# EASYEDA_JSON.net
KiCad netlist of a schematic drawn in EasyEDA
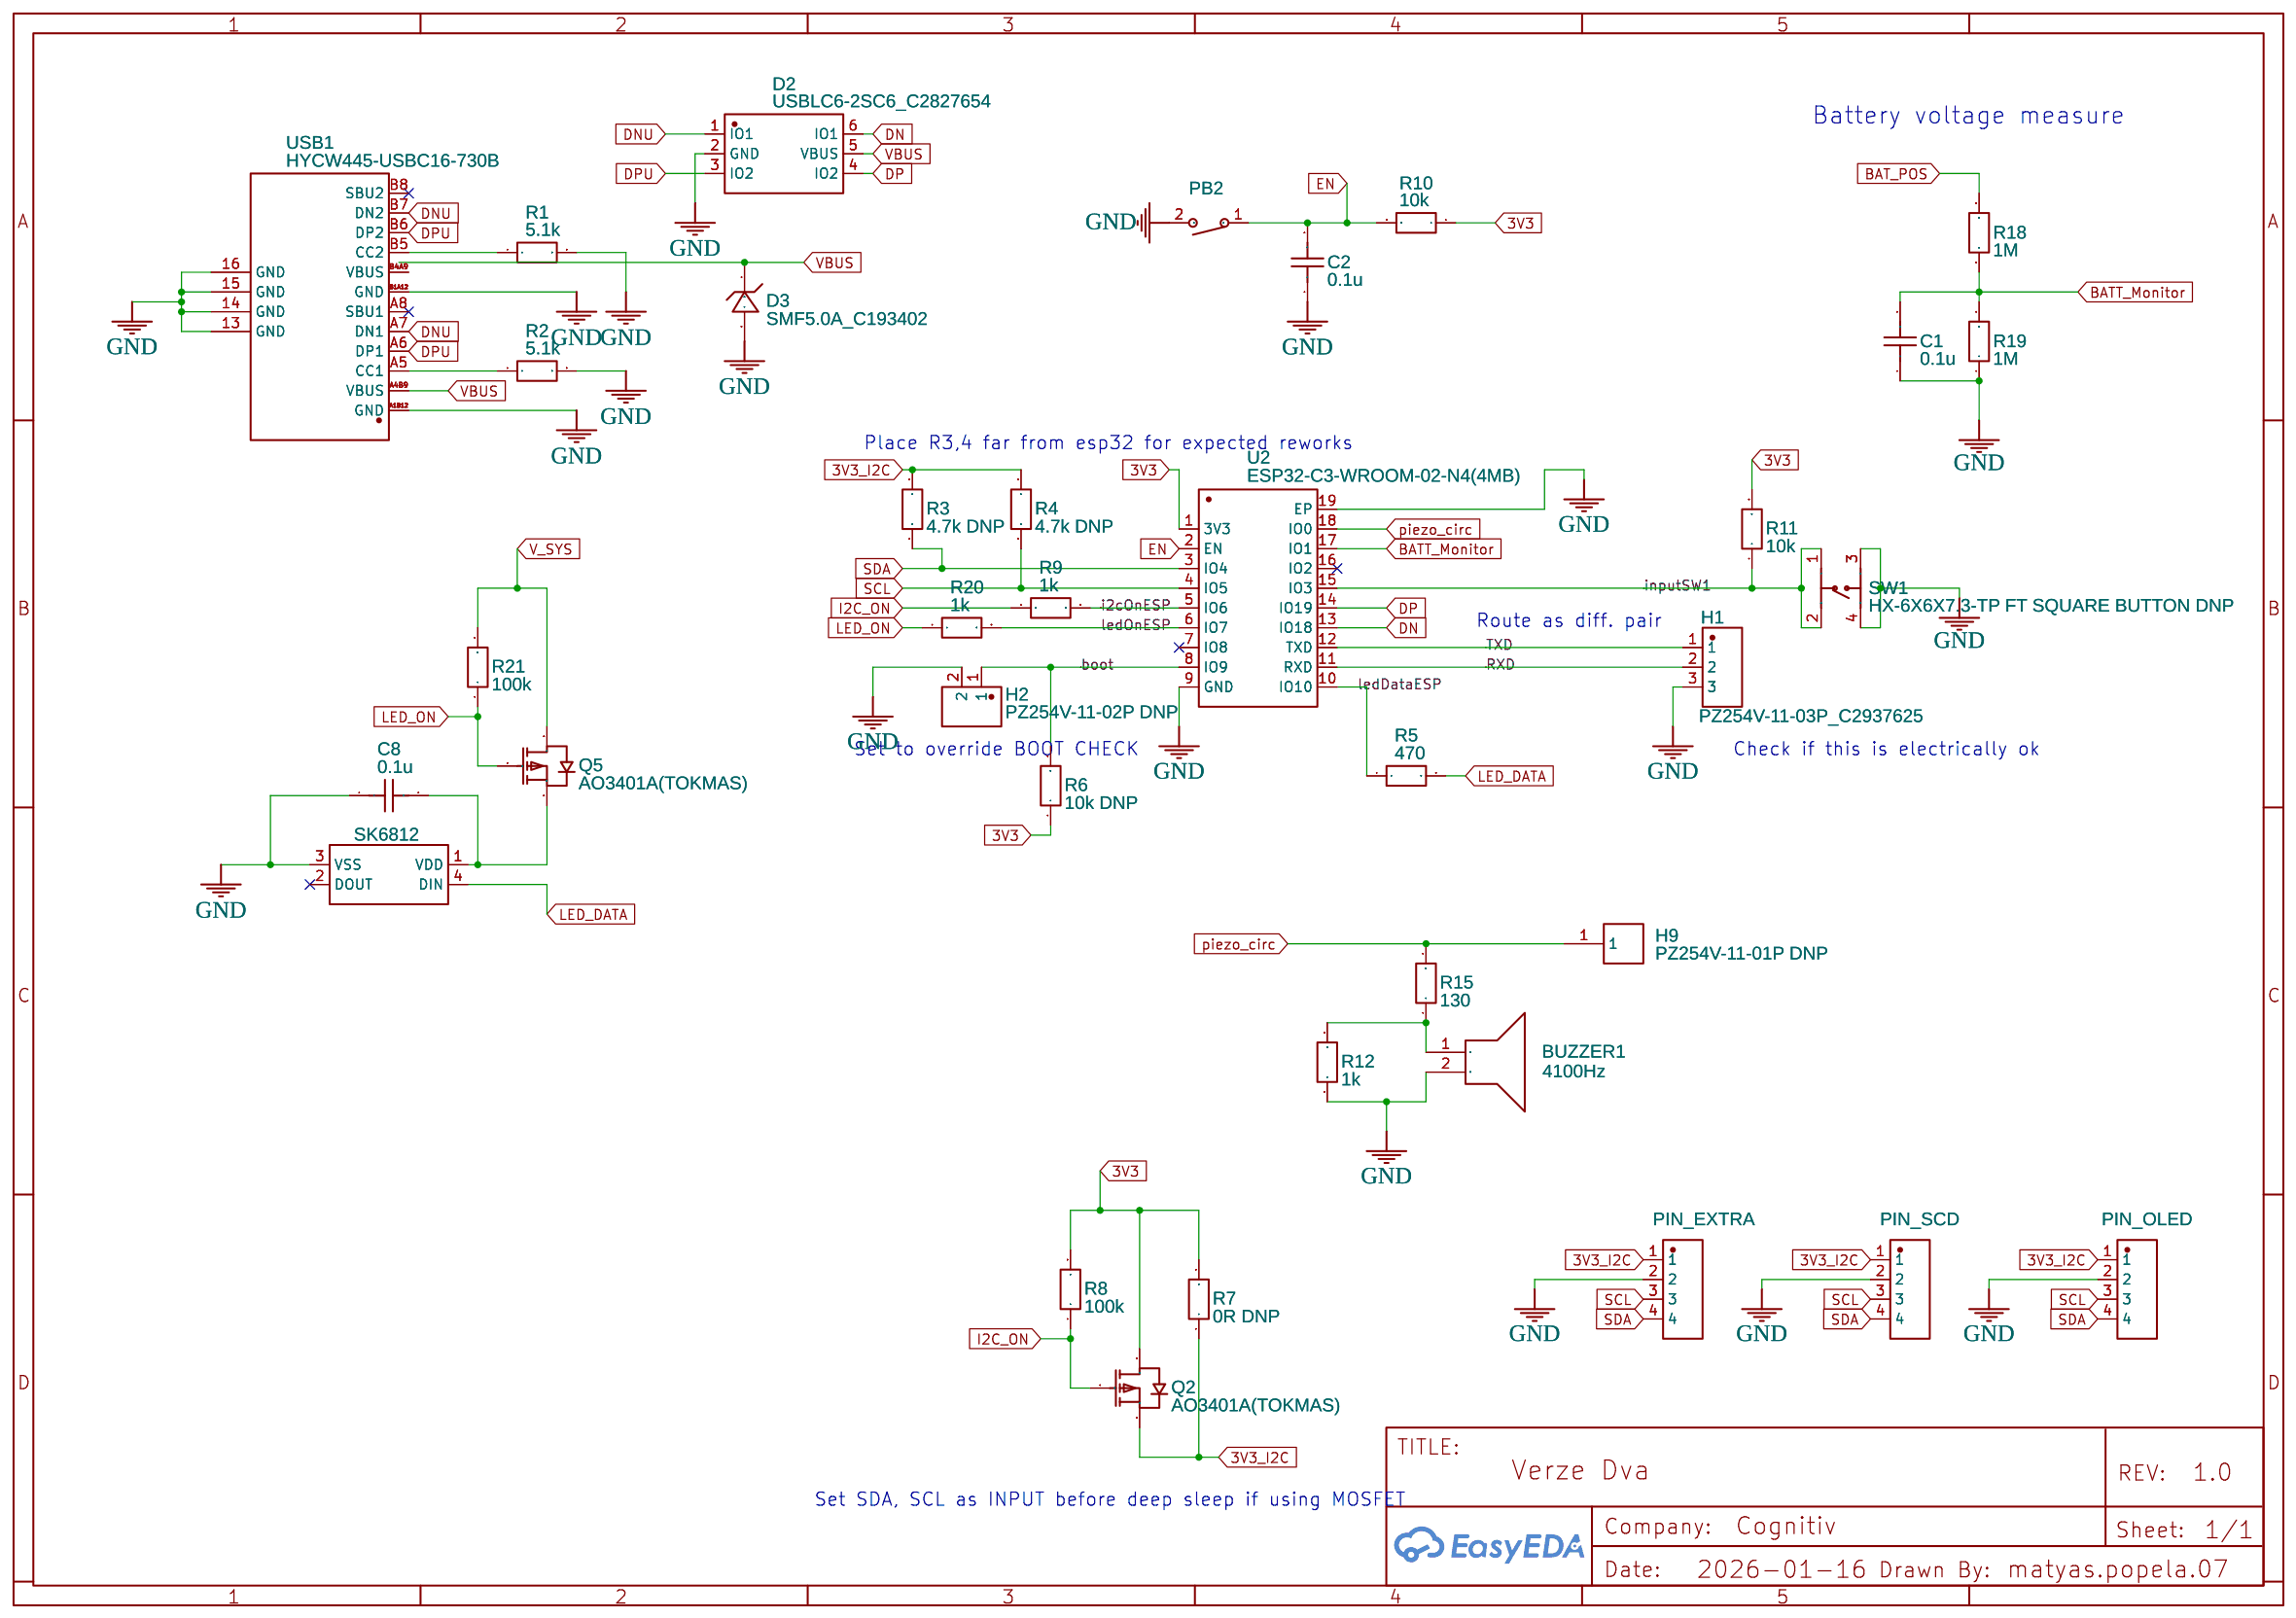
[diagram p0: Mainboard_C3]
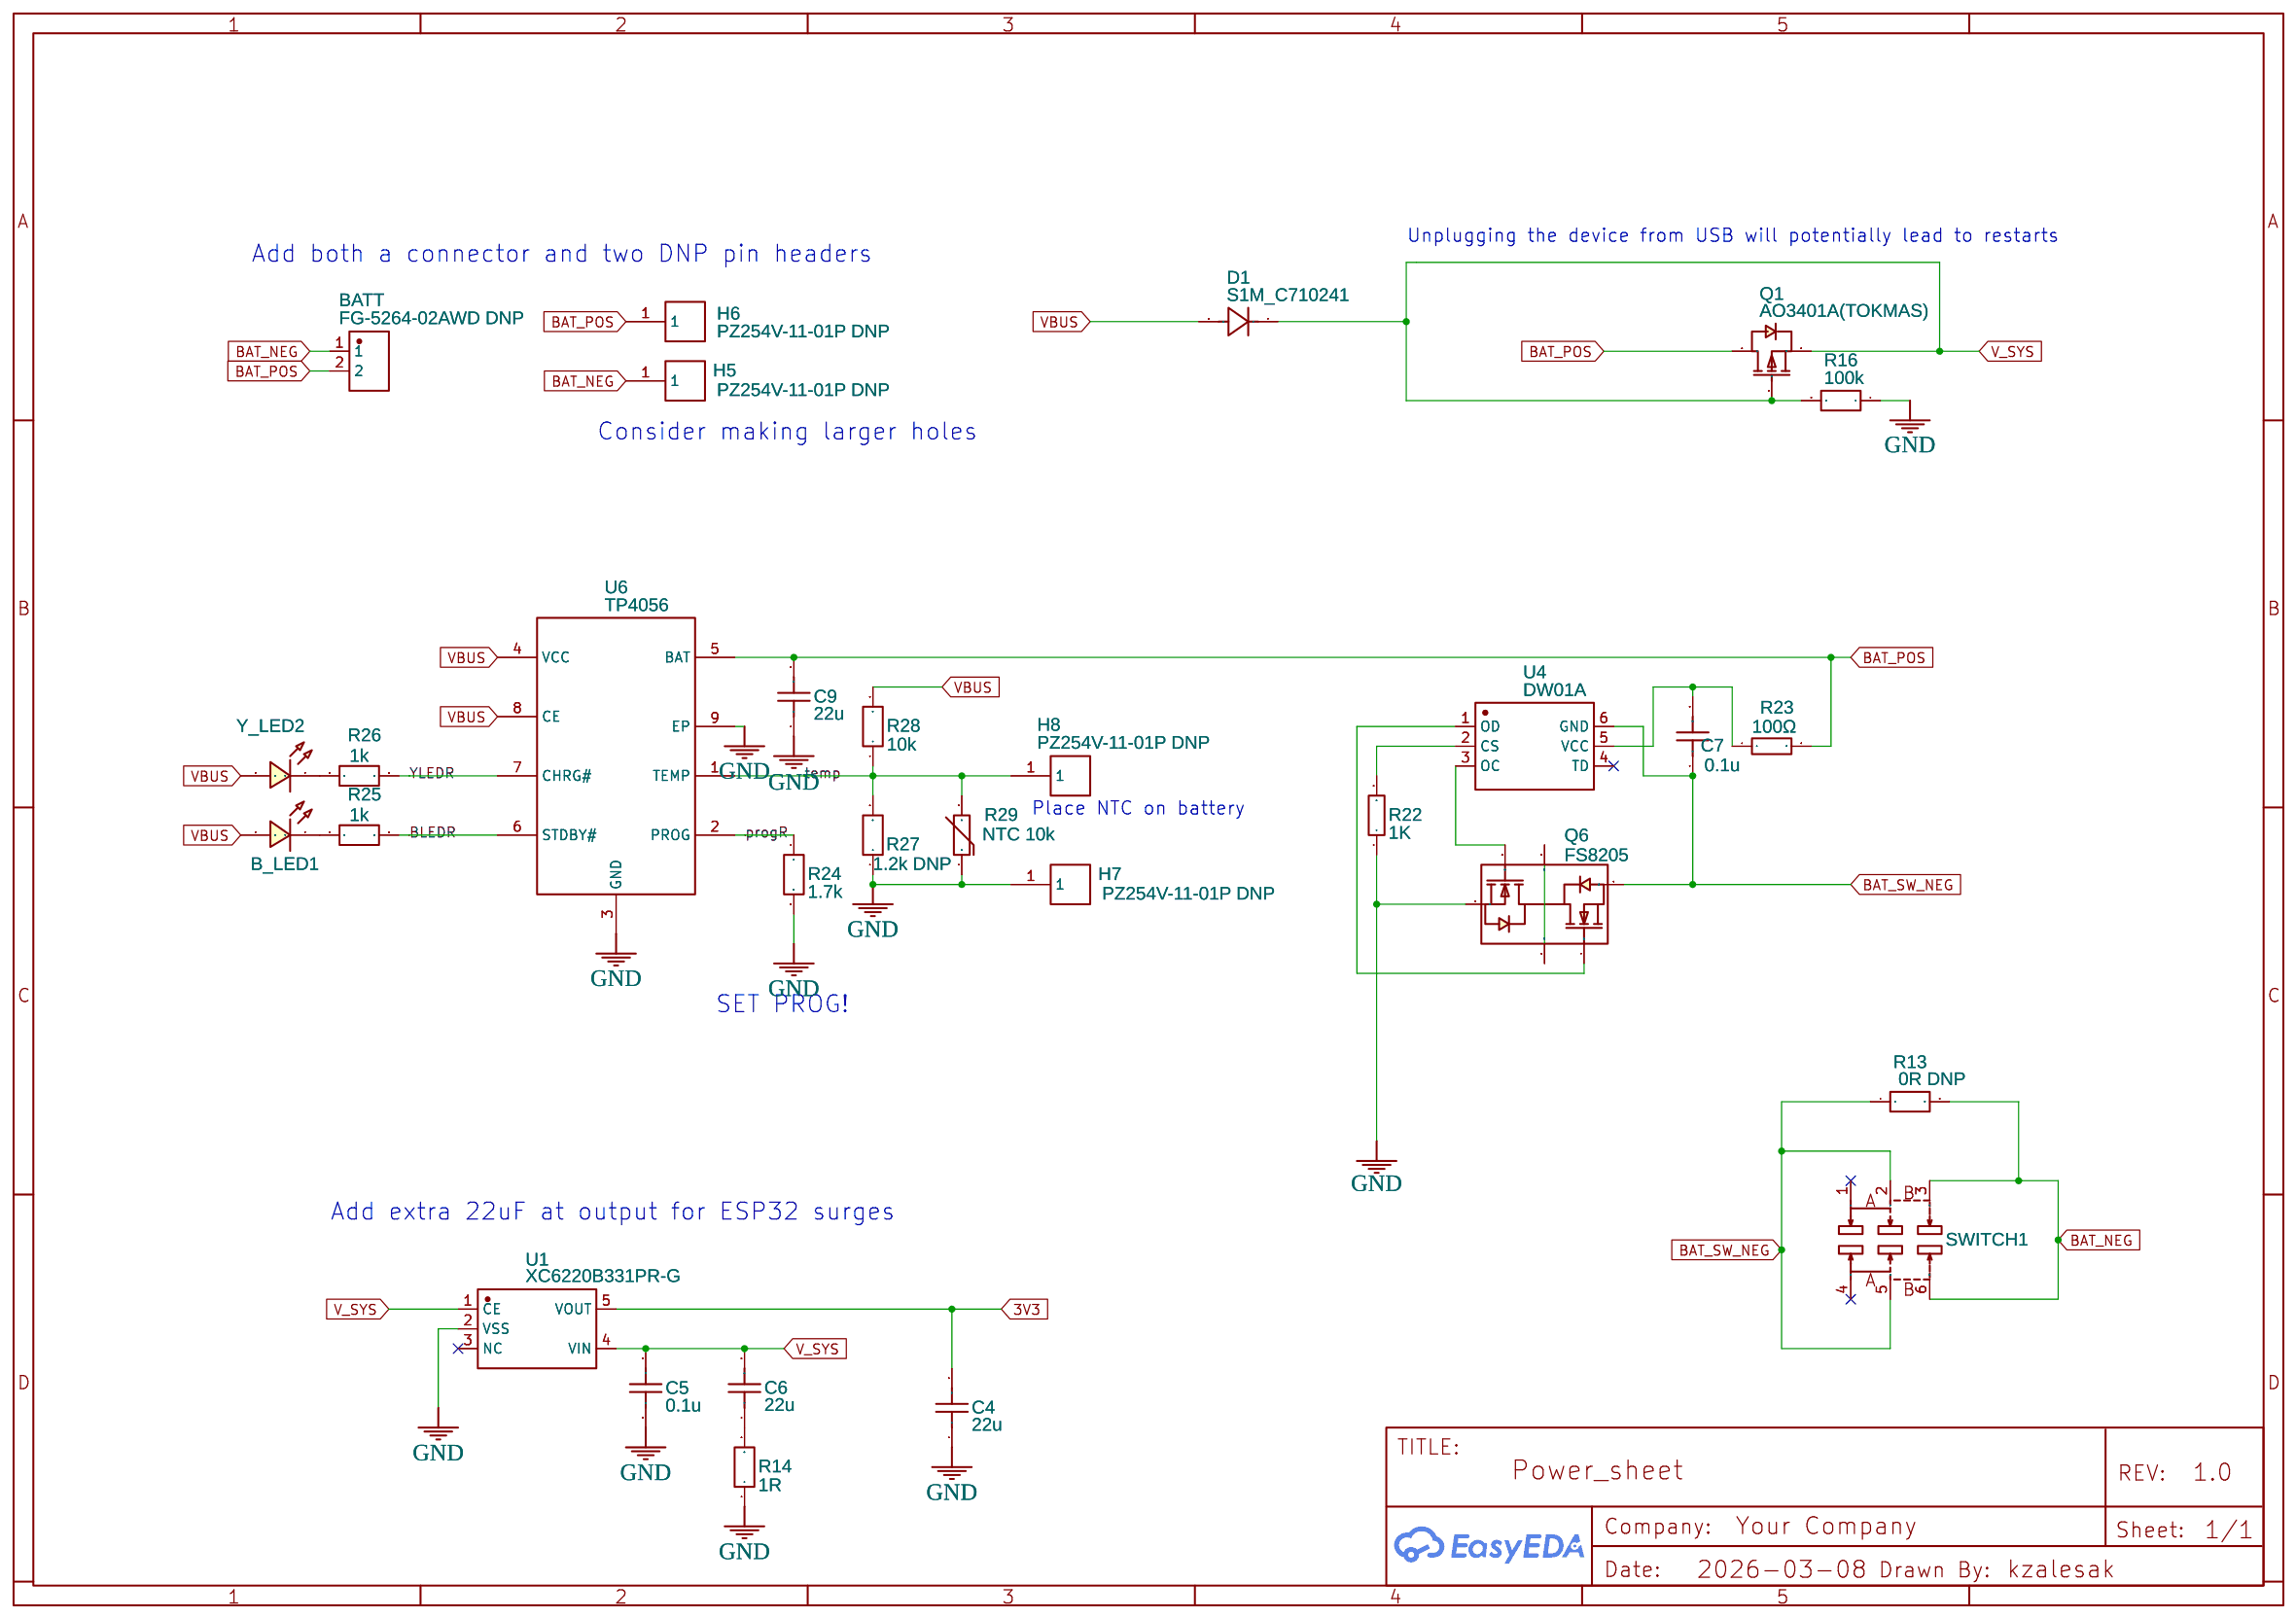
[diagram p1: Power_Management]

(export (version "E")
  (design (tool "Eeschema 10.0.6"))
  (components
    (comp (ref "BUZZER1")
      (value "4100Hz")
      (fields (field (name "Manufacturer Part") "FUET-1109") (field (name "Manufacturer") "FUET(福声科技)"))
      (libsource (lib "") (part "FST-1109"))
    )
    (comp (ref "C1")
      (value "0.1u")
      (fields
        (field (name "Manufacturer Part") "CC0603KRX7R9BB104")
        (field (name "Manufacturer") "YAGEO(国巨)")
      )
      (libsource (lib "") (part "C_0603_US"))
    )
    (comp (ref "C2")
      (value "0.1u")
      (fields
        (field (name "Manufacturer Part") "CC0603KRX7R9BB104")
        (field (name "Manufacturer") "YAGEO(国巨)")
      )
      (libsource (lib "") (part "C_0603_US"))
    )
    (comp (ref "C8")
      (value "0.1u")
      (fields
        (field (name "Manufacturer Part") "CC0603KRX7R9BB104")
        (field (name "Manufacturer") "YAGEO(国巨)")
      )
      (libsource (lib "") (part "C_0603_US_1"))
    )
    (comp (ref "D2")
      (value "USBLC6-2SC6_C2827654")
      (fields
        (field (name "Manufacturer Part") "USBLC6-2SC6")
        (field (name "Manufacturer") "TECH PUBLIC(台舟)")
      )
      (libsource (lib "") (part "USBLC6-2SC6_C2827654"))
    )
    (comp (ref "D3")
      (value "SMF5.0A_C193402")
      (fields (field (name "Manufacturer Part") "SMF5.0A") (field (name "Manufacturer") "MDD(辰达半导体)"))
      (libsource (lib "") (part "SMF5.0A_C193402"))
    )
    (comp (ref "H1")
      (value "PZ254V-11-03P_C2937625")
      (fields (field (name "Manufacturer Part") "PZ254V-11-03P") (field (name "Manufacturer") "XFCN(兴飞)"))
      (libsource (lib "") (part "PZ254V-11-03P_C2937625"))
    )
    (comp (ref "H2")
      (value "PZ254V-11-02P DNP")
      (fields (field (name "Manufacturer Part") "PZ254V-11-02P") (field (name "Manufacturer") "XFCN(兴飞)"))
      (libsource (lib "") (part "PZ254V-11-02P"))
    )
    (comp (ref "H9")
      (value "PZ254V-11-01P DNP")
      (fields (field (name "Manufacturer Part") "PZ254V-11-01P") (field (name "Manufacturer") "XFCN(兴飞)"))
      (libsource (lib "") (part "PZ254V-11-01P"))
    )
    (comp (ref "PB2")
      (value "HX 3X4X2-2P-1.6N TACTILE SWITCH DNP")
      (fields
        (field (name "Manufacturer Part") "HX 3x4x2-2P-1.6N TACTILE SWITCH")
        (field (name "Manufacturer") "hanxia(韩下)")
      )
      (libsource (lib "") (part "HX 3X4X2-2P-1.6N TACTILE SWITCH"))
    )
    (comp (ref "PIN_EXTRA")
      (value "2.54-1*4")
      (fields (field (name "Manufacturer") "ZHOURI(洲日)"))
      (libsource (lib "") (part "2.54-1*4_1"))
    )
    (comp (ref "PIN_OLED")
      (value "2.54-1*4")
      (fields (field (name "Manufacturer") "ZHOURI(洲日)"))
      (libsource (lib "") (part "2.54-1*4_2"))
    )
    (comp (ref "PIN_SCD")
      (value "2.54-1*4")
      (fields (field (name "Manufacturer") "ZHOURI(洲日)"))
      (libsource (lib "") (part "2.54-1*4"))
    )
    (comp (ref "Q2")
      (value "AO3401A(TOKMAS)")
      (fields (field (name "Manufacturer") "Tokmas(托克马斯)"))
      (libsource (lib "") (part "AO3401A(TOKMAS)"))
    )
    (comp (ref "Q5")
      (value "AO3401A(TOKMAS)")
      (fields (field (name "Manufacturer") "Tokmas(托克马斯)"))
      (libsource (lib "") (part "AO3401A(TOKMAS)"))
    )
    (comp (ref "R1") (value "5.1k") (libsource (lib "") (part "R_0603_EU_1")))
    (comp (ref "R2") (value "5.1k") (libsource (lib "") (part "R_0603_EU_1")))
    (comp (ref "R3") (value "4.7k DNP") (libsource (lib "") (part "R_0603_EU")))
    (comp (ref "R4") (value "4.7k DNP") (libsource (lib "") (part "R_0603_EU")))
    (comp (ref "R5") (value "470") (libsource (lib "") (part "R_0603_EU_1")))
    (comp (ref "R6") (value "10k DNP") (libsource (lib "") (part "R_0603_EU")))
    (comp (ref "R7") (value "0R DNP") (libsource (lib "") (part "R_0603_EU")))
    (comp (ref "R8") (value "100k") (libsource (lib "") (part "R_0603_EU")))
    (comp (ref "R9") (value "1k") (libsource (lib "") (part "R_0603_EU_1")))
    (comp (ref "R10") (value "10k") (libsource (lib "") (part "R_0603_EU_2")))
    (comp (ref "R11") (value "10k") (libsource (lib "") (part "R_0603_EU")))
    (comp (ref "R12") (value "1k") (libsource (lib "") (part "R_0603_EU")))
    (comp (ref "R15") (value "130") (libsource (lib "") (part "R_0603_EU")))
    (comp (ref "R18") (value "1M") (libsource (lib "") (part "R_0603_EU")))
    (comp (ref "R19") (value "1M") (libsource (lib "") (part "R_0603_EU")))
    (comp (ref "R20") (value "1k") (libsource (lib "") (part "R_0603_EU_1")))
    (comp (ref "R21") (value "100k") (libsource (lib "") (part "R_0603_EU")))
    (comp (ref "SK6812")
      (value "SK6812_C5378720")
      (fields (field (name "Manufacturer Part") "SK6812") (field (name "Manufacturer") "欧思科光电"))
      (libsource (lib "") (part "SK6812_C5378720"))
    )
    (comp (ref "SW1")
      (value "HX-6X6X7.3-TP FT SQUARE BUTTON DNP")
      (fields
        (field (name "Manufacturer Part") "HX-6x6x7.3-TP FT square button")
        (field (name "Manufacturer") "hanxia(韩下)")
      )
      (libsource (lib "") (part "HX-6X6X7.3-TP FT SQUARE BUTTON"))
    )
    (comp (ref "U2")
      (value "ESP32-C3-WROOM-02-N4(4MB)")
      (fields
        (field (name "Manufacturer Part") "ESP32-C3-WROOM-02-N4")
        (field (name "Manufacturer") "ESPRESSIF(乐鑫)")
      )
      (libsource (lib "") (part "ESP32-C3-WROOM-02-N4(4MB)"))
    )
    (comp (ref "USB1")
      (value "HYCW445-USBC16-730B")
      (fields (field (name "Manufacturer") "华宇创"))
      (libsource (lib "") (part "HYCW445-USBC16-730B"))
    )
    (comp (ref "BATT")
      (value "FG-5264-02AWD DNP")
      (fields (field (name "Manufacturer Part") "FG-5264-02AWD") (field (name "Manufacturer") "FG(富港)"))
      (libsource (lib "") (part "FG-5264-02AWD"))
    )
    (comp (ref "B_LED1")
      (value "LED-0603_R")
      (fields
        (field (name "Manufacturer Part") "19-217/R6C-AL1M2VY/3T")
        (field (name "Manufacturer") "EVERLIGHT(台湾亿光)")
      )
      (libsource (lib "") (part "LED-0603_R_1"))
    )
    (comp (ref "C4")
      (value "22u")
      (fields
        (field (name "Manufacturer Part") "CL21A226MAQNNNE")
        (field (name "Manufacturer") "SAMSUNG(三星)")
      )
      (libsource (lib "") (part "CL21A226MAQNNNE"))
    )
    (comp (ref "C5")
      (value "0.1u")
      (fields
        (field (name "Manufacturer Part") "CC0603KRX7R9BB104")
        (field (name "Manufacturer") "YAGEO(国巨)")
      )
      (libsource (lib "") (part "C_0603_US"))
    )
    (comp (ref "C6")
      (value "22u")
      (fields
        (field (name "Manufacturer Part") "CL21A226MAQNNNE")
        (field (name "Manufacturer") "SAMSUNG(三星)")
      )
      (libsource (lib "") (part "CL21A226MAQNNNE"))
    )
    (comp (ref "C7")
      (value "0.1u")
      (fields
        (field (name "Manufacturer Part") "CC0603KRX7R9BB104")
        (field (name "Manufacturer") "YAGEO(国巨)")
      )
      (libsource (lib "") (part "C_0603_US"))
    )
    (comp (ref "C9")
      (value "22u")
      (fields
        (field (name "Manufacturer Part") "CL21A226MAQNNNE")
        (field (name "Manufacturer") "SAMSUNG(三星)")
      )
      (libsource (lib "") (part "CL21A226MAQNNNE"))
    )
    (comp (ref "D1")
      (value "S1M_C710241")
      (fields (field (name "Manufacturer Part") "S1M") (field (name "Manufacturer") "DIODES(美台)"))
      (libsource (lib "") (part "S1M_C710241"))
    )
    (comp (ref "H5")
      (value "PZ254V-11-01P DNP")
      (fields (field (name "Manufacturer Part") "PZ254V-11-01P") (field (name "Manufacturer") "XFCN(兴飞)"))
      (libsource (lib "") (part "PZ254V-11-01P"))
    )
    (comp (ref "H6")
      (value "PZ254V-11-01P DNP")
      (fields (field (name "Manufacturer Part") "PZ254V-11-01P") (field (name "Manufacturer") "XFCN(兴飞)"))
      (libsource (lib "") (part "PZ254V-11-01P"))
    )
    (comp (ref "H7")
      (value "PZ254V-11-01P DNP")
      (fields (field (name "Manufacturer Part") "PZ254V-11-01P") (field (name "Manufacturer") "XFCN(兴飞)"))
      (libsource (lib "") (part "PZ254V-11-01P"))
    )
    (comp (ref "H8")
      (value "PZ254V-11-01P DNP")
      (fields (field (name "Manufacturer Part") "PZ254V-11-01P") (field (name "Manufacturer") "XFCN(兴飞)"))
      (libsource (lib "") (part "PZ254V-11-01P"))
    )
    (comp (ref "Q1")
      (value "AO3401A(TOKMAS)")
      (fields (field (name "Manufacturer") "Tokmas(托克马斯)"))
      (libsource (lib "") (part "AO3401A(TOKMAS)"))
    )
    (comp (ref "Q6")
      (value "FS8205")
      (fields (field (name "Manufacturer") "FORTUNE"))
      (libsource (lib "") (part "Unknown_775_-355"))
    )
    (comp (ref "R13") (value "0R DNP") (libsource (lib "") (part "R_0603_EU_1")))
    (comp (ref "R14") (value "1R") (libsource (lib "") (part "R_0603_EU_2")))
    (comp (ref "R16") (value "100k") (libsource (lib "") (part "R_0603_EU")))
    (comp (ref "R22")
      (value "1K")
      (fields (field (name "Manufacturer Part") "ERJ3GEYJ102V") (field (name "Manufacturer") "PANASONIC"))
      (libsource (lib "") (part "ERJ3GEYJ102V"))
    )
    (comp (ref "R23")
      (value "100Ω")
      (fields (field (name "Manufacturer Part") "0603WAJ0101T5E") (field (name "Manufacturer") "UniOhm"))
      (libsource (lib "") (part "0603WAJ0101T5E"))
    )
    (comp (ref "R24") (value "1.7k") (libsource (lib "") (part "R_0603_EU_3")))
    (comp (ref "R25") (value "1k") (libsource (lib "") (part "R_0603_EU_1")))
    (comp (ref "R26") (value "1k") (libsource (lib "") (part "R_0603_EU_1")))
    (comp (ref "R27") (value "1.2k DNP") (libsource (lib "") (part "R_0603_EU_2")))
    (comp (ref "R28") (value "10k") (libsource (lib "") (part "R_0603_EU_2")))
    (comp (ref "R29")
      (value "NTC 10k")
      (fields (field (name "Manufacturer Part") "CMFB103F3950FANT") (field (name "Manufacturer") "FH(风华)"))
      (libsource (lib "") (part "CMFB103F3950FANT"))
    )
    (comp (ref "SWITCH1")
      (value "MST22D18G2 125 DNP")
      (fields
        (field (name "Manufacturer Part") "MST22D18G2 125")
        (field (name "Manufacturer") "SHOU HAN(首韩)")
      )
      (libsource (lib "") (part "MST22D18G2 125"))
    )
    (comp (ref "U1")
      (value "XC6220B331PR-G")
      (fields (field (name "Manufacturer") "TOREX(特瑞仕)"))
      (libsource (lib "") (part "XC6220B331PR-G"))
    )
    (comp (ref "U4")
      (value "DW01A")
      (fields (field (name "Manufacturer") "PUOLOP"))
      (libsource (lib "") (part "Unknown_770_-435"))
    )
    (comp (ref "U6")
      (value "TP4056")
      (fields
        (field (name "Manufacturer Part") "TP4056-42-ESOP8")
        (field (name "Manufacturer") "TOPPOWER(南京拓微)")
      )
      (libsource (lib "") (part "TP4056"))
    )
    (comp (ref "Y_LED2")
      (value "LED-0603_R")
      (fields
        (field (name "Manufacturer Part") "19-217/R6C-AL1M2VY/3T")
        (field (name "Manufacturer") "EVERLIGHT(台湾亿光)")
      )
      (libsource (lib "") (part "LED-0603_R"))
    )
  )
  (nets
    (net (code "1") (name "3V3") (class "Default")
      (node (ref "C4") (pin "2") (pinfunction "2_2") (pintype "unspecified"))
      (node (ref "Q2") (pin "3") (pinfunction "D_3") (pintype "unspecified"))
      (node (ref "R10") (pin "1") (pinfunction "1_1") (pintype "unspecified"))
      (node (ref "R11") (pin "2") (pinfunction "2_2") (pintype "unspecified"))
      (node (ref "R6") (pin "1") (pinfunction "1_1") (pintype "unspecified"))
      (node (ref "R7") (pin "2") (pinfunction "2_2") (pintype "unspecified"))
      (node (ref "R8") (pin "2") (pinfunction "2_2") (pintype "unspecified"))
      (node (ref "U1") (pin "5") (pinfunction "VOUT_5") (pintype "unspecified"))
      (node (ref "U2") (pin "1") (pinfunction "3V3_1") (pintype "unspecified"))
    )
    (net (code "2") (name "3V3_I2C") (class "Default")
      (node (ref "PIN_EXTRA") (pin "1") (pinfunction "1_1") (pintype "unspecified"))
      (node (ref "PIN_OLED") (pin "1") (pinfunction "1_1") (pintype "unspecified"))
      (node (ref "PIN_SCD") (pin "1") (pinfunction "1_1") (pintype "unspecified"))
      (node (ref "Q2") (pin "2") (pinfunction "S_2") (pintype "unspecified"))
      (node (ref "R3") (pin "2") (pinfunction "2_2") (pintype "unspecified"))
      (node (ref "R4") (pin "2") (pinfunction "2_2") (pintype "unspecified"))
      (node (ref "R7") (pin "1") (pinfunction "1_1") (pintype "unspecified"))
    )
    (net (code "3") (name "BATT_Monitor") (class "Default")
      (node (ref "C1") (pin "2") (pinfunction "2_2") (pintype "unspecified"))
      (node (ref "R18") (pin "1") (pinfunction "1_1") (pintype "unspecified"))
      (node (ref "R19") (pin "2") (pinfunction "2_2") (pintype "unspecified"))
      (node (ref "U2") (pin "17") (pinfunction "IO1_17") (pintype "unspecified"))
    )
    (net (code "4") (name "BAT_NEG") (class "Default")
      (node (ref "BATT") (pin "1") (pinfunction "1_1") (pintype "unspecified"))
      (node (ref "H5") (pin "1") (pinfunction "1_1") (pintype "unspecified"))
      (node (ref "R13") (pin "2") (pinfunction "2_2") (pintype "unspecified"))
      (node (ref "SWITCH1") (pin "3") (pinfunction "3_3") (pintype "unspecified"))
      (node (ref "SWITCH1") (pin "6") (pinfunction "6_6") (pintype "unspecified"))
    )
    (net (code "5") (name "BAT_POS") (class "Default")
      (node (ref "BATT") (pin "2") (pinfunction "2_2") (pintype "unspecified"))
      (node (ref "C9") (pin "2") (pinfunction "2_2") (pintype "unspecified"))
      (node (ref "H6") (pin "1") (pinfunction "1_1") (pintype "unspecified"))
      (node (ref "Q1") (pin "3") (pinfunction "D_3") (pintype "unspecified"))
      (node (ref "R18") (pin "2") (pinfunction "2_2") (pintype "unspecified"))
      (node (ref "R23") (pin "2") (pinfunction "2_2") (pintype "input"))
      (node (ref "U6") (pin "5") (pinfunction "BAT_5") (pintype "unspecified"))
    )
    (net (code "6") (name "BAT_SW_NEG") (class "Default")
      (node (ref "C7") (pin "1") (pinfunction "1_1") (pintype "unspecified"))
      (node (ref "Q6") (pin "3") (pinfunction "S2_3") (pintype "unspecified"))
      (node (ref "R13") (pin "1") (pinfunction "1_1") (pintype "unspecified"))
      (node (ref "SWITCH1") (pin "2") (pinfunction "2_2") (pintype "unspecified"))
      (node (ref "SWITCH1") (pin "5") (pinfunction "5_5") (pintype "unspecified"))
      (node (ref "U4") (pin "6") (pinfunction "GND_6") (pintype "unspecified"))
    )
    (net (code "7") (name "BLEDR") (class "Default")
      (node (ref "R25") (pin "2") (pinfunction "2_2") (pintype "unspecified"))
      (node (ref "U6") (pin "6") (pinfunction "STDBY#_6") (pintype "unspecified"))
    )
    (net (code "8") (name "DN") (class "Default")
      (node (ref "D2") (pin "6") (pinfunction "IO1_6") (pintype "unspecified"))
      (node (ref "U2") (pin "13") (pinfunction "IO18_13") (pintype "unspecified"))
    )
    (net (code "9") (name "DNU") (class "Default")
      (node (ref "D2") (pin "1") (pinfunction "IO1_1") (pintype "unspecified"))
      (node (ref "USB1") (pin "A7") (pinfunction "DN1_A7") (pintype "unspecified"))
      (node (ref "USB1") (pin "B7") (pinfunction "DN2_B7") (pintype "unspecified"))
    )
    (net (code "10") (name "DP") (class "Default")
      (node (ref "D2") (pin "4") (pinfunction "IO2_4") (pintype "unspecified"))
      (node (ref "U2") (pin "14") (pinfunction "IO19_14") (pintype "unspecified"))
    )
    (net (code "11") (name "DPU") (class "Default")
      (node (ref "D2") (pin "3") (pinfunction "IO2_3") (pintype "unspecified"))
      (node (ref "USB1") (pin "A6") (pinfunction "DP1_A6") (pintype "unspecified"))
      (node (ref "USB1") (pin "B6") (pinfunction "DP2_B6") (pintype "unspecified"))
    )
    (net (code "12") (name "EN") (class "Default")
      (node (ref "C2") (pin "2") (pinfunction "2_2") (pintype "unspecified"))
      (node (ref "PB2") (pin "1") (pinfunction "1_1") (pintype "unspecified"))
      (node (ref "R10") (pin "2") (pinfunction "2_2") (pintype "unspecified"))
      (node (ref "U2") (pin "2") (pinfunction "EN_2") (pintype "unspecified"))
    )
    (net (code "13") (name "GND") (class "Default")
      (node (ref "BUZZER1") (pin "2") (pinfunction "2_2") (pintype "unspecified"))
      (node (ref "C1") (pin "1") (pinfunction "1_1") (pintype "unspecified"))
      (node (ref "C2") (pin "1") (pinfunction "1_1") (pintype "unspecified"))
      (node (ref "C4") (pin "1") (pinfunction "1_1") (pintype "unspecified"))
      (node (ref "C5") (pin "1") (pinfunction "1_1") (pintype "unspecified"))
      (node (ref "C8") (pin "1") (pinfunction "1_1") (pintype "unspecified"))
      (node (ref "C9") (pin "1") (pinfunction "1_1") (pintype "unspecified"))
      (node (ref "D2") (pin "2") (pinfunction "GND_2") (pintype "unspecified"))
      (node (ref "D3") (pin "2") (pinfunction "A_2") (pintype "unspecified"))
      (node (ref "H1") (pin "3") (pinfunction "3_3") (pintype "unspecified"))
      (node (ref "H2") (pin "2") (pinfunction "2_2") (pintype "unspecified"))
      (node (ref "H7") (pin "1") (pinfunction "1_1") (pintype "unspecified"))
      (node (ref "PB2") (pin "2") (pinfunction "2_2") (pintype "unspecified"))
      (node (ref "PIN_EXTRA") (pin "2") (pinfunction "2_2") (pintype "unspecified"))
      (node (ref "PIN_OLED") (pin "2") (pinfunction "2_2") (pintype "unspecified"))
      (node (ref "PIN_SCD") (pin "2") (pinfunction "2_2") (pintype "unspecified"))
      (node (ref "Q6") (pin "1") (pinfunction "S1_1") (pintype "unspecified"))
      (node (ref "R1") (pin "2") (pinfunction "2_2") (pintype "unspecified"))
      (node (ref "R12") (pin "1") (pinfunction "1_1") (pintype "unspecified"))
      (node (ref "R14") (pin "1") (pinfunction "1_1") (pintype "unspecified"))
      (node (ref "R16") (pin "1") (pinfunction "1_1") (pintype "unspecified"))
      (node (ref "R19") (pin "1") (pinfunction "1_1") (pintype "unspecified"))
      (node (ref "R2") (pin "2") (pinfunction "2_2") (pintype "unspecified"))
      (node (ref "R22") (pin "1") (pinfunction "1_1") (pintype "unspecified"))
      (node (ref "R24") (pin "2") (pinfunction "2_2") (pintype "unspecified"))
      (node (ref "R27") (pin "1") (pinfunction "1_1") (pintype "unspecified"))
      (node (ref "R29") (pin "1") (pinfunction "1_1") (pintype "input"))
      (node (ref "SK6812") (pin "3") (pinfunction "VSS_3") (pintype "unspecified"))
      (node (ref "SW1") (pin "3") (pinfunction "C_3") (pintype "unspecified"))
      (node (ref "SW1") (pin "4") (pinfunction "D_4") (pintype "unspecified"))
      (node (ref "U1") (pin "2") (pinfunction "VSS_2") (pintype "unspecified"))
      (node (ref "U2") (pin "19") (pinfunction "EP_19") (pintype "unspecified"))
      (node (ref "U2") (pin "9") (pinfunction "GND_9") (pintype "unspecified"))
      (node (ref "U6") (pin "3") (pinfunction "GND_3") (pintype "unspecified"))
      (node (ref "U6") (pin "9") (pinfunction "EP_9") (pintype "unspecified"))
      (node (ref "USB1") (pin "13") (pinfunction "GND_13") (pintype "unspecified"))
      (node (ref "USB1") (pin "14") (pinfunction "GND_14") (pintype "unspecified"))
      (node (ref "USB1") (pin "15") (pinfunction "GND_15") (pintype "unspecified"))
      (node (ref "USB1") (pin "16") (pinfunction "GND_16") (pintype "unspecified"))
      (node (ref "USB1") (pin "A1B12") (pinfunction "GND_A1B12") (pintype "unspecified"))
      (node (ref "USB1") (pin "B1A12") (pinfunction "GND_B1A12") (pintype "unspecified"))
    )
    (net (code "14") (name "I2C_ON") (class "Default")
      (node (ref "Q2") (pin "1") (pinfunction "G_1") (pintype "unspecified"))
      (node (ref "R8") (pin "1") (pinfunction "1_1") (pintype "unspecified"))
      (node (ref "R9") (pin "1") (pinfunction "1_1") (pintype "unspecified"))
    )
    (net (code "15") (name "LED_DATA") (class "Default")
      (node (ref "R5") (pin "2") (pinfunction "2_2") (pintype "unspecified"))
      (node (ref "SK6812") (pin "4") (pinfunction "DIN_4") (pintype "unspecified"))
    )
    (net (code "16") (name "LED_ON") (class "Default")
      (node (ref "Q5") (pin "1") (pinfunction "G_1") (pintype "unspecified"))
      (node (ref "R20") (pin "1") (pinfunction "1_1") (pintype "unspecified"))
      (node (ref "R21") (pin "1") (pinfunction "1_1") (pintype "unspecified"))
    )
    (net (code "17") (name "Net-(BUZZER1-Pad1)") (class "Default")
      (node (ref "BUZZER1") (pin "1") (pinfunction "1_1") (pintype "unspecified"))
      (node (ref "R12") (pin "2") (pinfunction "2_2") (pintype "unspecified"))
      (node (ref "R15") (pin "1") (pinfunction "1_1") (pintype "unspecified"))
    )
    (net (code "18") (name "Net-(B_LED1-Pad2)") (class "Default")
      (node (ref "B_LED1") (pin "2") (pinfunction "2_2") (pintype "unspecified"))
      (node (ref "R25") (pin "1") (pinfunction "1_1") (pintype "unspecified"))
    )
    (net (code "19") (name "Net-(C6-Pad1)") (class "Default")
      (node (ref "C6") (pin "1") (pinfunction "1_1") (pintype "unspecified"))
      (node (ref "R14") (pin "2") (pinfunction "2_2") (pintype "unspecified"))
    )
    (net (code "20") (name "Net-(Q5-S)") (class "Default")
      (node (ref "C8") (pin "2") (pinfunction "2_2") (pintype "unspecified"))
      (node (ref "Q5") (pin "2") (pinfunction "S_2") (pintype "unspecified"))
      (node (ref "SK6812") (pin "1") (pinfunction "VDD_1") (pintype "unspecified"))
    )
    (net (code "21") (name "Net-(Q6-D12-Pad2)") (class "Default")
      (node (ref "Q6") (pin "2") (pinfunction "D12_2") (pintype "unspecified"))
      (node (ref "Q6") (pin "5") (pinfunction "D12_5") (pintype "unspecified"))
    )
    (net (code "22") (name "Net-(Q6-G1)") (class "Default")
      (node (ref "Q6") (pin "6") (pinfunction "G1_6") (pintype "unspecified"))
      (node (ref "U4") (pin "3") (pinfunction "OC_3") (pintype "unspecified"))
    )
    (net (code "23") (name "Net-(Q6-G2)") (class "Default")
      (node (ref "Q6") (pin "4") (pinfunction "G2_4") (pintype "unspecified"))
      (node (ref "U4") (pin "1") (pinfunction "OD_1") (pintype "unspecified"))
    )
    (net (code "24") (name "Net-(R26-Pad1)") (class "Default")
      (node (ref "R26") (pin "1") (pinfunction "1_1") (pintype "unspecified"))
      (node (ref "Y_LED2") (pin "2") (pinfunction "2_2") (pintype "unspecified"))
    )
    (net (code "25") (name "Net-(U4-CS)") (class "Default")
      (node (ref "R22") (pin "2") (pinfunction "2_2") (pintype "unspecified"))
      (node (ref "U4") (pin "2") (pinfunction "CS_2") (pintype "unspecified"))
    )
    (net (code "26") (name "Net-(U4-VCC)") (class "Default")
      (node (ref "C7") (pin "2") (pinfunction "2_2") (pintype "unspecified"))
      (node (ref "R23") (pin "1") (pinfunction "1_1") (pintype "input"))
      (node (ref "U4") (pin "5") (pinfunction "VCC_5") (pintype "unspecified"))
    )
    (net (code "27") (name "Net-(USB1-CC1)") (class "Default")
      (node (ref "R2") (pin "1") (pinfunction "1_1") (pintype "unspecified"))
      (node (ref "USB1") (pin "A5") (pinfunction "CC1_A5") (pintype "unspecified"))
    )
    (net (code "28") (name "Net-(USB1-CC2)") (class "Default")
      (node (ref "R1") (pin "1") (pinfunction "1_1") (pintype "unspecified"))
      (node (ref "USB1") (pin "B5") (pinfunction "CC2_B5") (pintype "unspecified"))
    )
    (net (code "29") (name "RXD") (class "Default")
      (node (ref "H1") (pin "2") (pinfunction "2_2") (pintype "unspecified"))
      (node (ref "U2") (pin "11") (pinfunction "RXD_11") (pintype "unspecified"))
    )
    (net (code "30") (name "SCL") (class "Default")
      (node (ref "PIN_EXTRA") (pin "3") (pinfunction "3_3") (pintype "unspecified"))
      (node (ref "PIN_OLED") (pin "3") (pinfunction "3_3") (pintype "unspecified"))
      (node (ref "PIN_SCD") (pin "3") (pinfunction "3_3") (pintype "unspecified"))
      (node (ref "R4") (pin "1") (pinfunction "1_1") (pintype "unspecified"))
      (node (ref "U2") (pin "4") (pinfunction "IO5_4") (pintype "unspecified"))
    )
    (net (code "31") (name "SDA") (class "Default")
      (node (ref "PIN_EXTRA") (pin "4") (pinfunction "4_4") (pintype "unspecified"))
      (node (ref "PIN_OLED") (pin "4") (pinfunction "4_4") (pintype "unspecified"))
      (node (ref "PIN_SCD") (pin "4") (pinfunction "4_4") (pintype "unspecified"))
      (node (ref "R3") (pin "1") (pinfunction "1_1") (pintype "unspecified"))
      (node (ref "U2") (pin "3") (pinfunction "IO4_3") (pintype "unspecified"))
    )
    (net (code "32") (name "TXD") (class "Default")
      (node (ref "H1") (pin "1") (pinfunction "1_1") (pintype "unspecified"))
      (node (ref "U2") (pin "12") (pinfunction "TXD_12") (pintype "unspecified"))
    )
    (net (code "33") (name "VBUS") (class "Default")
      (node (ref "B_LED1") (pin "1") (pinfunction "1_1") (pintype "unspecified"))
      (node (ref "D1") (pin "2") (pinfunction "A_2") (pintype "unspecified"))
      (node (ref "D2") (pin "5") (pinfunction "VBUS_5") (pintype "unspecified"))
      (node (ref "D3") (pin "1") (pinfunction "C_1") (pintype "unspecified"))
      (node (ref "R28") (pin "2") (pinfunction "2_2") (pintype "unspecified"))
      (node (ref "U6") (pin "4") (pinfunction "VCC_4") (pintype "unspecified"))
      (node (ref "U6") (pin "8") (pinfunction "CE_8") (pintype "unspecified"))
      (node (ref "USB1") (pin "A4B9") (pinfunction "VBUS_A4B9") (pintype "unspecified"))
      (node (ref "Y_LED2") (pin "1") (pinfunction "1_1") (pintype "unspecified"))
    )
    (net (code "34") (name "V_SYS") (class "Default")
      (node (ref "C5") (pin "2") (pinfunction "2_2") (pintype "unspecified"))
      (node (ref "C6") (pin "2") (pinfunction "2_2") (pintype "unspecified"))
      (node (ref "D1") (pin "1") (pinfunction "K_1") (pintype "unspecified"))
      (node (ref "Q1") (pin "1") (pinfunction "G_1") (pintype "unspecified"))
      (node (ref "Q1") (pin "2") (pinfunction "S_2") (pintype "unspecified"))
      (node (ref "Q5") (pin "3") (pinfunction "D_3") (pintype "unspecified"))
      (node (ref "R16") (pin "2") (pinfunction "2_2") (pintype "unspecified"))
      (node (ref "R21") (pin "2") (pinfunction "2_2") (pintype "unspecified"))
      (node (ref "U1") (pin "1") (pinfunction "CE_1") (pintype "unspecified"))
      (node (ref "U1") (pin "4") (pinfunction "VIN_4") (pintype "unspecified"))
    )
    (net (code "35") (name "YLEDR") (class "Default")
      (node (ref "R26") (pin "2") (pinfunction "2_2") (pintype "unspecified"))
      (node (ref "U6") (pin "7") (pinfunction "CHRG#_7") (pintype "unspecified"))
    )
    (net (code "36") (name "boot") (class "Default")
      (node (ref "H2") (pin "1") (pinfunction "1_1") (pintype "unspecified"))
      (node (ref "R6") (pin "2") (pinfunction "2_2") (pintype "unspecified"))
      (node (ref "U2") (pin "8") (pinfunction "IO9_8") (pintype "unspecified"))
    )
    (net (code "37") (name "i2cOnESP") (class "Default")
      (node (ref "R9") (pin "2") (pinfunction "2_2") (pintype "unspecified"))
      (node (ref "U2") (pin "5") (pinfunction "IO6_5") (pintype "unspecified"))
    )
    (net (code "38") (name "inputSW1") (class "Default")
      (node (ref "R11") (pin "1") (pinfunction "1_1") (pintype "unspecified"))
      (node (ref "SW1") (pin "1") (pinfunction "A_1") (pintype "unspecified"))
      (node (ref "SW1") (pin "2") (pinfunction "B_2") (pintype "unspecified"))
      (node (ref "U2") (pin "15") (pinfunction "IO3_15") (pintype "unspecified"))
    )
    (net (code "39") (name "ledDataESP") (class "Default")
      (node (ref "R5") (pin "1") (pinfunction "1_1") (pintype "unspecified"))
      (node (ref "U2") (pin "10") (pinfunction "IO10_10") (pintype "unspecified"))
    )
    (net (code "40") (name "ledOnESP") (class "Default")
      (node (ref "R20") (pin "2") (pinfunction "2_2") (pintype "unspecified"))
      (node (ref "U2") (pin "6") (pinfunction "IO7_6") (pintype "unspecified"))
    )
    (net (code "41") (name "piezo_circ") (class "Default")
      (node (ref "H9") (pin "1") (pinfunction "1_1") (pintype "unspecified"))
      (node (ref "R15") (pin "2") (pinfunction "2_2") (pintype "unspecified"))
      (node (ref "U2") (pin "18") (pinfunction "IO0_18") (pintype "unspecified"))
    )
    (net (code "42") (name "progR") (class "Default")
      (node (ref "R24") (pin "1") (pinfunction "1_1") (pintype "unspecified"))
      (node (ref "U6") (pin "2") (pinfunction "PROG_2") (pintype "unspecified"))
    )
    (net (code "43") (name "temp") (class "Default")
      (node (ref "H8") (pin "1") (pinfunction "1_1") (pintype "unspecified"))
      (node (ref "R27") (pin "2") (pinfunction "2_2") (pintype "unspecified"))
      (node (ref "R28") (pin "1") (pinfunction "1_1") (pintype "unspecified"))
      (node (ref "R29") (pin "2") (pinfunction "2_2") (pintype "input"))
      (node (ref "U6") (pin "1") (pinfunction "TEMP_1") (pintype "unspecified"))
    )
    (net (code "44") (name "unconnected-(SK6812-DOUT-Pad2)") (class "Default")
      (node (ref "SK6812") (pin "2") (pinfunction "DOUT_2") (pintype "unspecified+no_connect"))
    )
    (net (code "45") (name "unconnected-(SWITCH1-Pad1)") (class "Default")
      (node (ref "SWITCH1") (pin "1") (pinfunction "1_1") (pintype "unspecified+no_connect"))
    )
    (net (code "46") (name "unconnected-(SWITCH1-Pad4)") (class "Default")
      (node (ref "SWITCH1") (pin "4") (pinfunction "4_4") (pintype "unspecified+no_connect"))
    )
    (net (code "47") (name "unconnected-(U1-NC-Pad3)") (class "Default")
      (node (ref "U1") (pin "3") (pinfunction "NC_3") (pintype "unspecified+no_connect"))
    )
    (net (code "48") (name "unconnected-(U2-IO2-Pad16)") (class "Default")
      (node (ref "U2") (pin "16") (pinfunction "IO2_16") (pintype "unspecified+no_connect"))
    )
    (net (code "49") (name "unconnected-(U2-IO8-Pad7)") (class "Default")
      (node (ref "U2") (pin "7") (pinfunction "IO8_7") (pintype "unspecified+no_connect"))
    )
    (net (code "50") (name "unconnected-(U4-TD-Pad4)") (class "Default")
      (node (ref "U4") (pin "4") (pinfunction "TD_4") (pintype "unspecified+no_connect"))
    )
    (net (code "51") (name "unconnected-(USB1-SBU1-PadA8)") (class "Default")
      (node (ref "USB1") (pin "A8") (pinfunction "SBU1_A8") (pintype "unspecified+no_connect"))
    )
    (net (code "52") (name "unconnected-(USB1-SBU2-PadB8)") (class "Default")
      (node (ref "USB1") (pin "B8") (pinfunction "SBU2_B8") (pintype "unspecified+no_connect"))
    )
    (net (code "53") (name "unconnected-(USB1-VBUS-PadB4A9)") (class "Default")
      (node (ref "USB1") (pin "B4A9") (pinfunction "VBUS_B4A9") (pintype "unspecified"))
    )
  )
)
